# Connector.net
KiCad netlist of a schematic drawn in Altium Designer
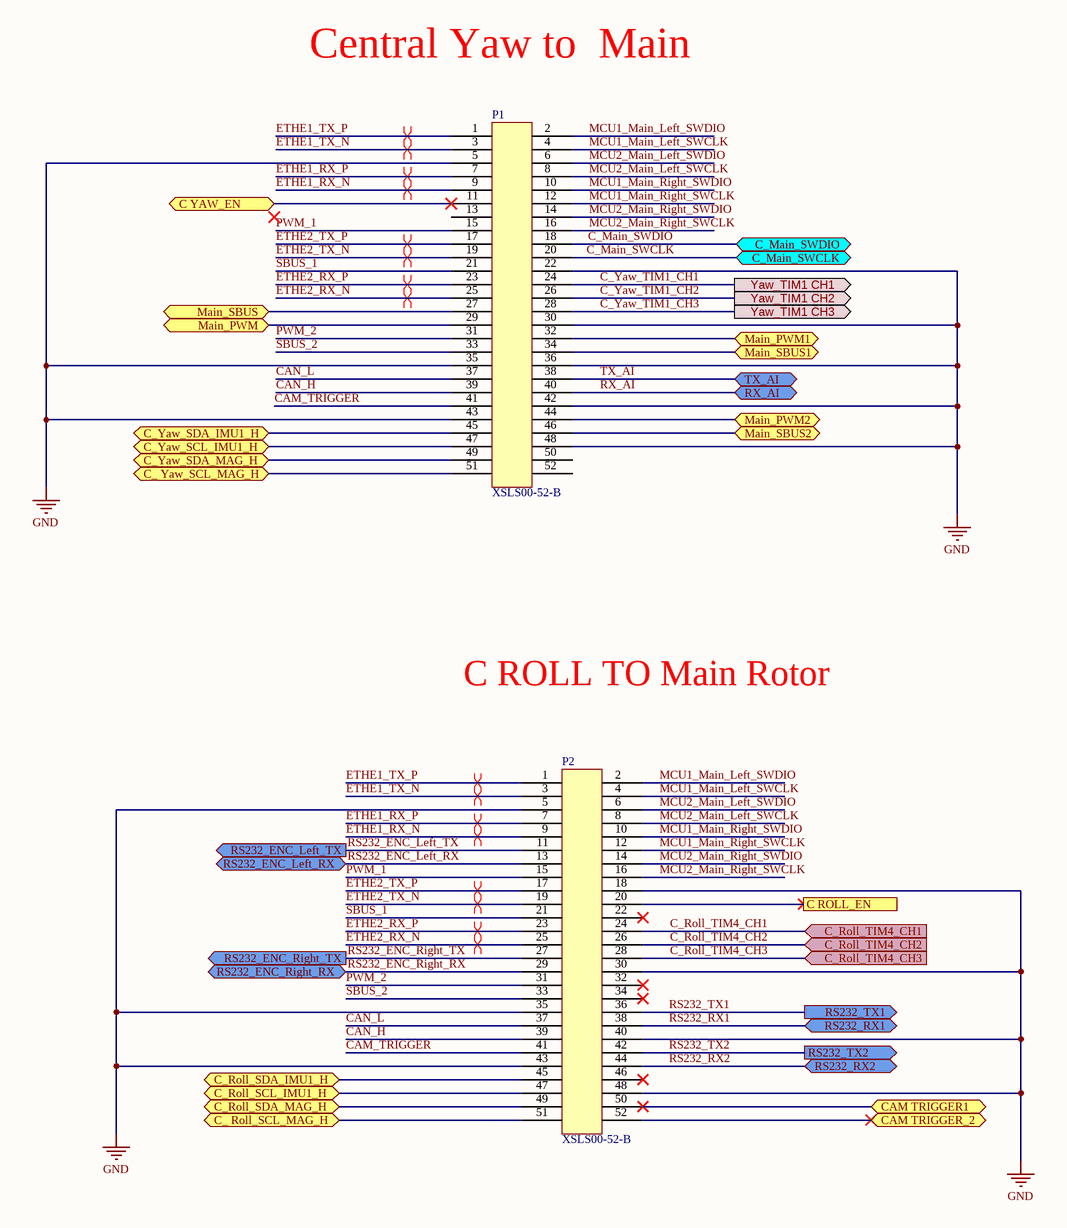
[diagram p0: Connector.SchDoc]

(export (version "E")
  (design (tool "Eeschema 10.0.6"))
  (components
    (comp (ref "P1")
      (value "XSLS00-52-B")
      (footprint "XSXL52")
      (libsource (lib "Hera_Sight_PixyU2") (part "XSLS00-52-B"))
    )
    (comp (ref "P2")
      (value "XSLS00-52-B")
      (footprint "XSXL52")
      (libsource (lib "Hera_Sight_PixyU2") (part "XSLS00-52-B"))
    )
  )
  (nets
    (net (code "1") (name "/C ROLL_EN") (class "Default")
      (node (ref "P2") (pin "20") (pintype "passive+no_connect"))
    )
    (net (code "2") (name "/C YAW_EN") (class "Default")
      (node (ref "P1") (pin "11") (pintype "passive+no_connect"))
    )
    (net (code "3") (name "/CAM TRIGGER1") (class "Default")
      (node (ref "P2") (pin "50") (pintype "passive+no_connect"))
    )
    (net (code "4") (name "/CAM TRIGGER_2") (class "Default")
      (node (ref "P2") (pin "52") (pintype "passive+no_connect"))
    )
    (net (code "5") (name "/CAM_TRIGGER") (class "Default")
      (node (ref "P1") (pin "41") (pintype "passive"))
      (node (ref "P2") (pin "41") (pintype "passive"))
    )
    (net (code "6") (name "/CAN_H") (class "Default")
      (node (ref "P1") (pin "39") (pintype "passive"))
      (node (ref "P2") (pin "39") (pintype "passive"))
    )
    (net (code "7") (name "/CAN_L") (class "Default")
      (node (ref "P1") (pin "37") (pintype "passive"))
      (node (ref "P2") (pin "37") (pintype "passive"))
    )
    (net (code "8") (name "/C_ Roll_SCL_MAG_H") (class "Default")
      (node (ref "P2") (pin "51") (pintype "passive"))
    )
    (net (code "9") (name "/C_ Yaw_SCL_MAG_H") (class "Default")
      (node (ref "P1") (pin "51") (pintype "passive"))
    )
    (net (code "10") (name "/C_Main_SWCLK") (class "Default")
      (node (ref "P1") (pin "20") (pintype "passive"))
    )
    (net (code "11") (name "/C_Main_SWDIO") (class "Default")
      (node (ref "P1") (pin "18") (pintype "passive"))
    )
    (net (code "12") (name "/C_Roll_SCL_IMU1_H") (class "Default")
      (node (ref "P2") (pin "47") (pintype "passive"))
    )
    (net (code "13") (name "/C_Roll_SDA_IMU1_H") (class "Default")
      (node (ref "P2") (pin "45") (pintype "passive"))
    )
    (net (code "14") (name "/C_Roll_SDA_MAG_H") (class "Default")
      (node (ref "P2") (pin "49") (pintype "passive"))
    )
    (net (code "15") (name "/C_Roll_TIM4_CH1") (class "Default")
      (node (ref "P2") (pin "24") (pintype "passive"))
    )
    (net (code "16") (name "/C_Roll_TIM4_CH2") (class "Default")
      (node (ref "P2") (pin "26") (pintype "passive"))
    )
    (net (code "17") (name "/C_Roll_TIM4_CH3") (class "Default")
      (node (ref "P2") (pin "28") (pintype "passive"))
    )
    (net (code "18") (name "/C_Yaw_SCL_IMU1_H") (class "Default")
      (node (ref "P1") (pin "47") (pintype "passive"))
    )
    (net (code "19") (name "/C_Yaw_SDA_IMU1_H") (class "Default")
      (node (ref "P1") (pin "45") (pintype "passive"))
    )
    (net (code "20") (name "/C_Yaw_SDA_MAG_H") (class "Default")
      (node (ref "P1") (pin "49") (pintype "passive"))
    )
    (net (code "21") (name "/C_Yaw_TIM1_CH1") (class "Default")
      (node (ref "P1") (pin "24") (pintype "passive"))
    )
    (net (code "22") (name "/C_Yaw_TIM1_CH2") (class "Default")
      (node (ref "P1") (pin "26") (pintype "passive"))
    )
    (net (code "23") (name "/C_Yaw_TIM1_CH3") (class "Default")
      (node (ref "P1") (pin "28") (pintype "passive"))
    )
    (net (code "24") (name "/ETHE1_RX_N") (class "Default")
      (node (ref "P1") (pin "9") (pintype "passive"))
      (node (ref "P2") (pin "9") (pintype "passive"))
    )
    (net (code "25") (name "/ETHE1_RX_P") (class "Default")
      (node (ref "P1") (pin "7") (pintype "passive"))
      (node (ref "P2") (pin "7") (pintype "passive"))
    )
    (net (code "26") (name "/ETHE1_TX_N") (class "Default")
      (node (ref "P1") (pin "3") (pintype "passive"))
      (node (ref "P2") (pin "3") (pintype "passive"))
    )
    (net (code "27") (name "/ETHE1_TX_P") (class "Default")
      (node (ref "P1") (pin "1") (pintype "passive"))
      (node (ref "P2") (pin "1") (pintype "passive"))
    )
    (net (code "28") (name "/ETHE2_RX_N") (class "Default")
      (node (ref "P1") (pin "25") (pintype "passive"))
      (node (ref "P2") (pin "25") (pintype "passive"))
    )
    (net (code "29") (name "/ETHE2_RX_P") (class "Default")
      (node (ref "P1") (pin "23") (pintype "passive"))
      (node (ref "P2") (pin "23") (pintype "passive"))
    )
    (net (code "30") (name "/ETHE2_TX_N") (class "Default")
      (node (ref "P1") (pin "19") (pintype "passive"))
      (node (ref "P2") (pin "19") (pintype "passive"))
    )
    (net (code "31") (name "/ETHE2_TX_P") (class "Default")
      (node (ref "P1") (pin "17") (pintype "passive"))
      (node (ref "P2") (pin "17") (pintype "passive"))
    )
    (net (code "32") (name "/MCU1_Main_Left_SWCLK") (class "Default")
      (node (ref "P1") (pin "4") (pintype "passive"))
      (node (ref "P2") (pin "4") (pintype "passive"))
    )
    (net (code "33") (name "/MCU1_Main_Left_SWDIO") (class "Default")
      (node (ref "P1") (pin "2") (pintype "passive"))
      (node (ref "P2") (pin "2") (pintype "passive"))
    )
    (net (code "34") (name "/MCU1_Main_Right_SWCLK") (class "Default")
      (node (ref "P1") (pin "12") (pintype "passive"))
      (node (ref "P2") (pin "12") (pintype "passive"))
    )
    (net (code "35") (name "/MCU1_Main_Right_SWDIO") (class "Default")
      (node (ref "P1") (pin "10") (pintype "passive"))
      (node (ref "P2") (pin "10") (pintype "passive"))
    )
    (net (code "36") (name "/MCU2_Main_Left_SWCLK") (class "Default")
      (node (ref "P1") (pin "8") (pintype "passive"))
      (node (ref "P2") (pin "8") (pintype "passive"))
    )
    (net (code "37") (name "/MCU2_Main_Left_SWDIO") (class "Default")
      (node (ref "P1") (pin "6") (pintype "passive"))
      (node (ref "P2") (pin "6") (pintype "passive"))
    )
    (net (code "38") (name "/MCU2_Main_Right_SWCLK") (class "Default")
      (node (ref "P1") (pin "16") (pintype "passive"))
      (node (ref "P2") (pin "16") (pintype "passive"))
    )
    (net (code "39") (name "/MCU2_Main_Right_SWDIO") (class "Default")
      (node (ref "P1") (pin "14") (pintype "passive"))
      (node (ref "P2") (pin "14") (pintype "passive"))
    )
    (net (code "40") (name "/Main_PWM") (class "Default") (node (ref "P1") (pin "29") (pintype "passive")))
    (net (code "41") (name "/Main_PWM1") (class "Default") (node (ref "P1") (pin "32") (pintype "passive")))
    (net (code "42") (name "/Main_PWM2") (class "Default") (node (ref "P1") (pin "44") (pintype "passive")))
    (net (code "43") (name "/Main_SBUS") (class "Default") (node (ref "P1") (pin "27") (pintype "passive")))
    (net (code "44") (name "/Main_SBUS1") (class "Default") (node (ref "P1") (pin "34") (pintype "passive")))
    (net (code "45") (name "/Main_SBUS2") (class "Default") (node (ref "P1") (pin "46") (pintype "passive")))
    (net (code "46") (name "/PWM_1") (class "Default")
      (node (ref "P1") (pin "15") (pintype "passive"))
      (node (ref "P2") (pin "15") (pintype "passive"))
    )
    (net (code "47") (name "/PWM_2") (class "Default")
      (node (ref "P1") (pin "31") (pintype "passive"))
      (node (ref "P2") (pin "31") (pintype "passive"))
    )
    (net (code "48") (name "/RS232_ENC_Left_RX") (class "Default")
      (node (ref "P2") (pin "13") (pintype "passive"))
    )
    (net (code "49") (name "/RS232_ENC_Left_TX") (class "Default")
      (node (ref "P2") (pin "11") (pintype "passive"))
    )
    (net (code "50") (name "/RS232_ENC_Right_RX") (class "Default")
      (node (ref "P2") (pin "29") (pintype "passive"))
    )
    (net (code "51") (name "/RS232_ENC_Right_TX") (class "Default")
      (node (ref "P2") (pin "27") (pintype "passive"))
    )
    (net (code "52") (name "/RS232_RX1") (class "Default") (node (ref "P2") (pin "38") (pintype "passive")))
    (net (code "53") (name "/RS232_RX2") (class "Default") (node (ref "P2") (pin "44") (pintype "passive")))
    (net (code "54") (name "/RS232_TX1") (class "Default") (node (ref "P2") (pin "36") (pintype "passive")))
    (net (code "55") (name "/RS232_TX2") (class "Default") (node (ref "P2") (pin "42") (pintype "passive")))
    (net (code "56") (name "/RX_AI") (class "Default") (node (ref "P1") (pin "40") (pintype "passive")))
    (net (code "57") (name "/SBUS_1") (class "Default")
      (node (ref "P1") (pin "21") (pintype "passive"))
      (node (ref "P2") (pin "21") (pintype "passive"))
    )
    (net (code "58") (name "/SBUS_2") (class "Default")
      (node (ref "P1") (pin "33") (pintype "passive"))
      (node (ref "P2") (pin "33") (pintype "passive"))
    )
    (net (code "59") (name "/TX_AI") (class "Default") (node (ref "P1") (pin "38") (pintype "passive")))
    (net (code "60") (name "GND") (class "Default")
      (node (ref "P1") (pin "22") (pintype "passive"))
      (node (ref "P1") (pin "30") (pintype "passive"))
      (node (ref "P1") (pin "35") (pintype "passive"))
      (node (ref "P1") (pin "36") (pintype "passive"))
      (node (ref "P1") (pin "42") (pintype "passive"))
      (node (ref "P1") (pin "43") (pintype "passive"))
      (node (ref "P1") (pin "48") (pintype "passive"))
      (node (ref "P1") (pin "5") (pintype "passive"))
      (node (ref "P2") (pin "18") (pintype "passive"))
      (node (ref "P2") (pin "30") (pintype "passive"))
      (node (ref "P2") (pin "35") (pintype "passive"))
      (node (ref "P2") (pin "40") (pintype "passive"))
      (node (ref "P2") (pin "43") (pintype "passive"))
      (node (ref "P2") (pin "48") (pintype "passive"))
      (node (ref "P2") (pin "5") (pintype "passive"))
    )
    (net (code "61") (name "unconnected-(P1-Pad13)") (class "Default")
      (node (ref "P1") (pin "13") (pintype "passive"))
    )
    (net (code "62") (name "unconnected-(P1-Pad50)") (class "Default")
      (node (ref "P1") (pin "50") (pintype "passive"))
    )
    (net (code "63") (name "unconnected-(P1-Pad52)") (class "Default")
      (node (ref "P1") (pin "52") (pintype "passive"))
    )
    (net (code "64") (name "unconnected-(P2-Pad22)") (class "Default")
      (node (ref "P2") (pin "22") (pintype "passive+no_connect"))
    )
    (net (code "65") (name "unconnected-(P2-Pad32)") (class "Default")
      (node (ref "P2") (pin "32") (pintype "passive+no_connect"))
    )
    (net (code "66") (name "unconnected-(P2-Pad34)") (class "Default")
      (node (ref "P2") (pin "34") (pintype "passive+no_connect"))
    )
    (net (code "67") (name "unconnected-(P2-Pad46)") (class "Default")
      (node (ref "P2") (pin "46") (pintype "passive+no_connect"))
    )
  )
)
